# SDC_2.net
KiCad netlist of a schematic drawn in Altium Designer
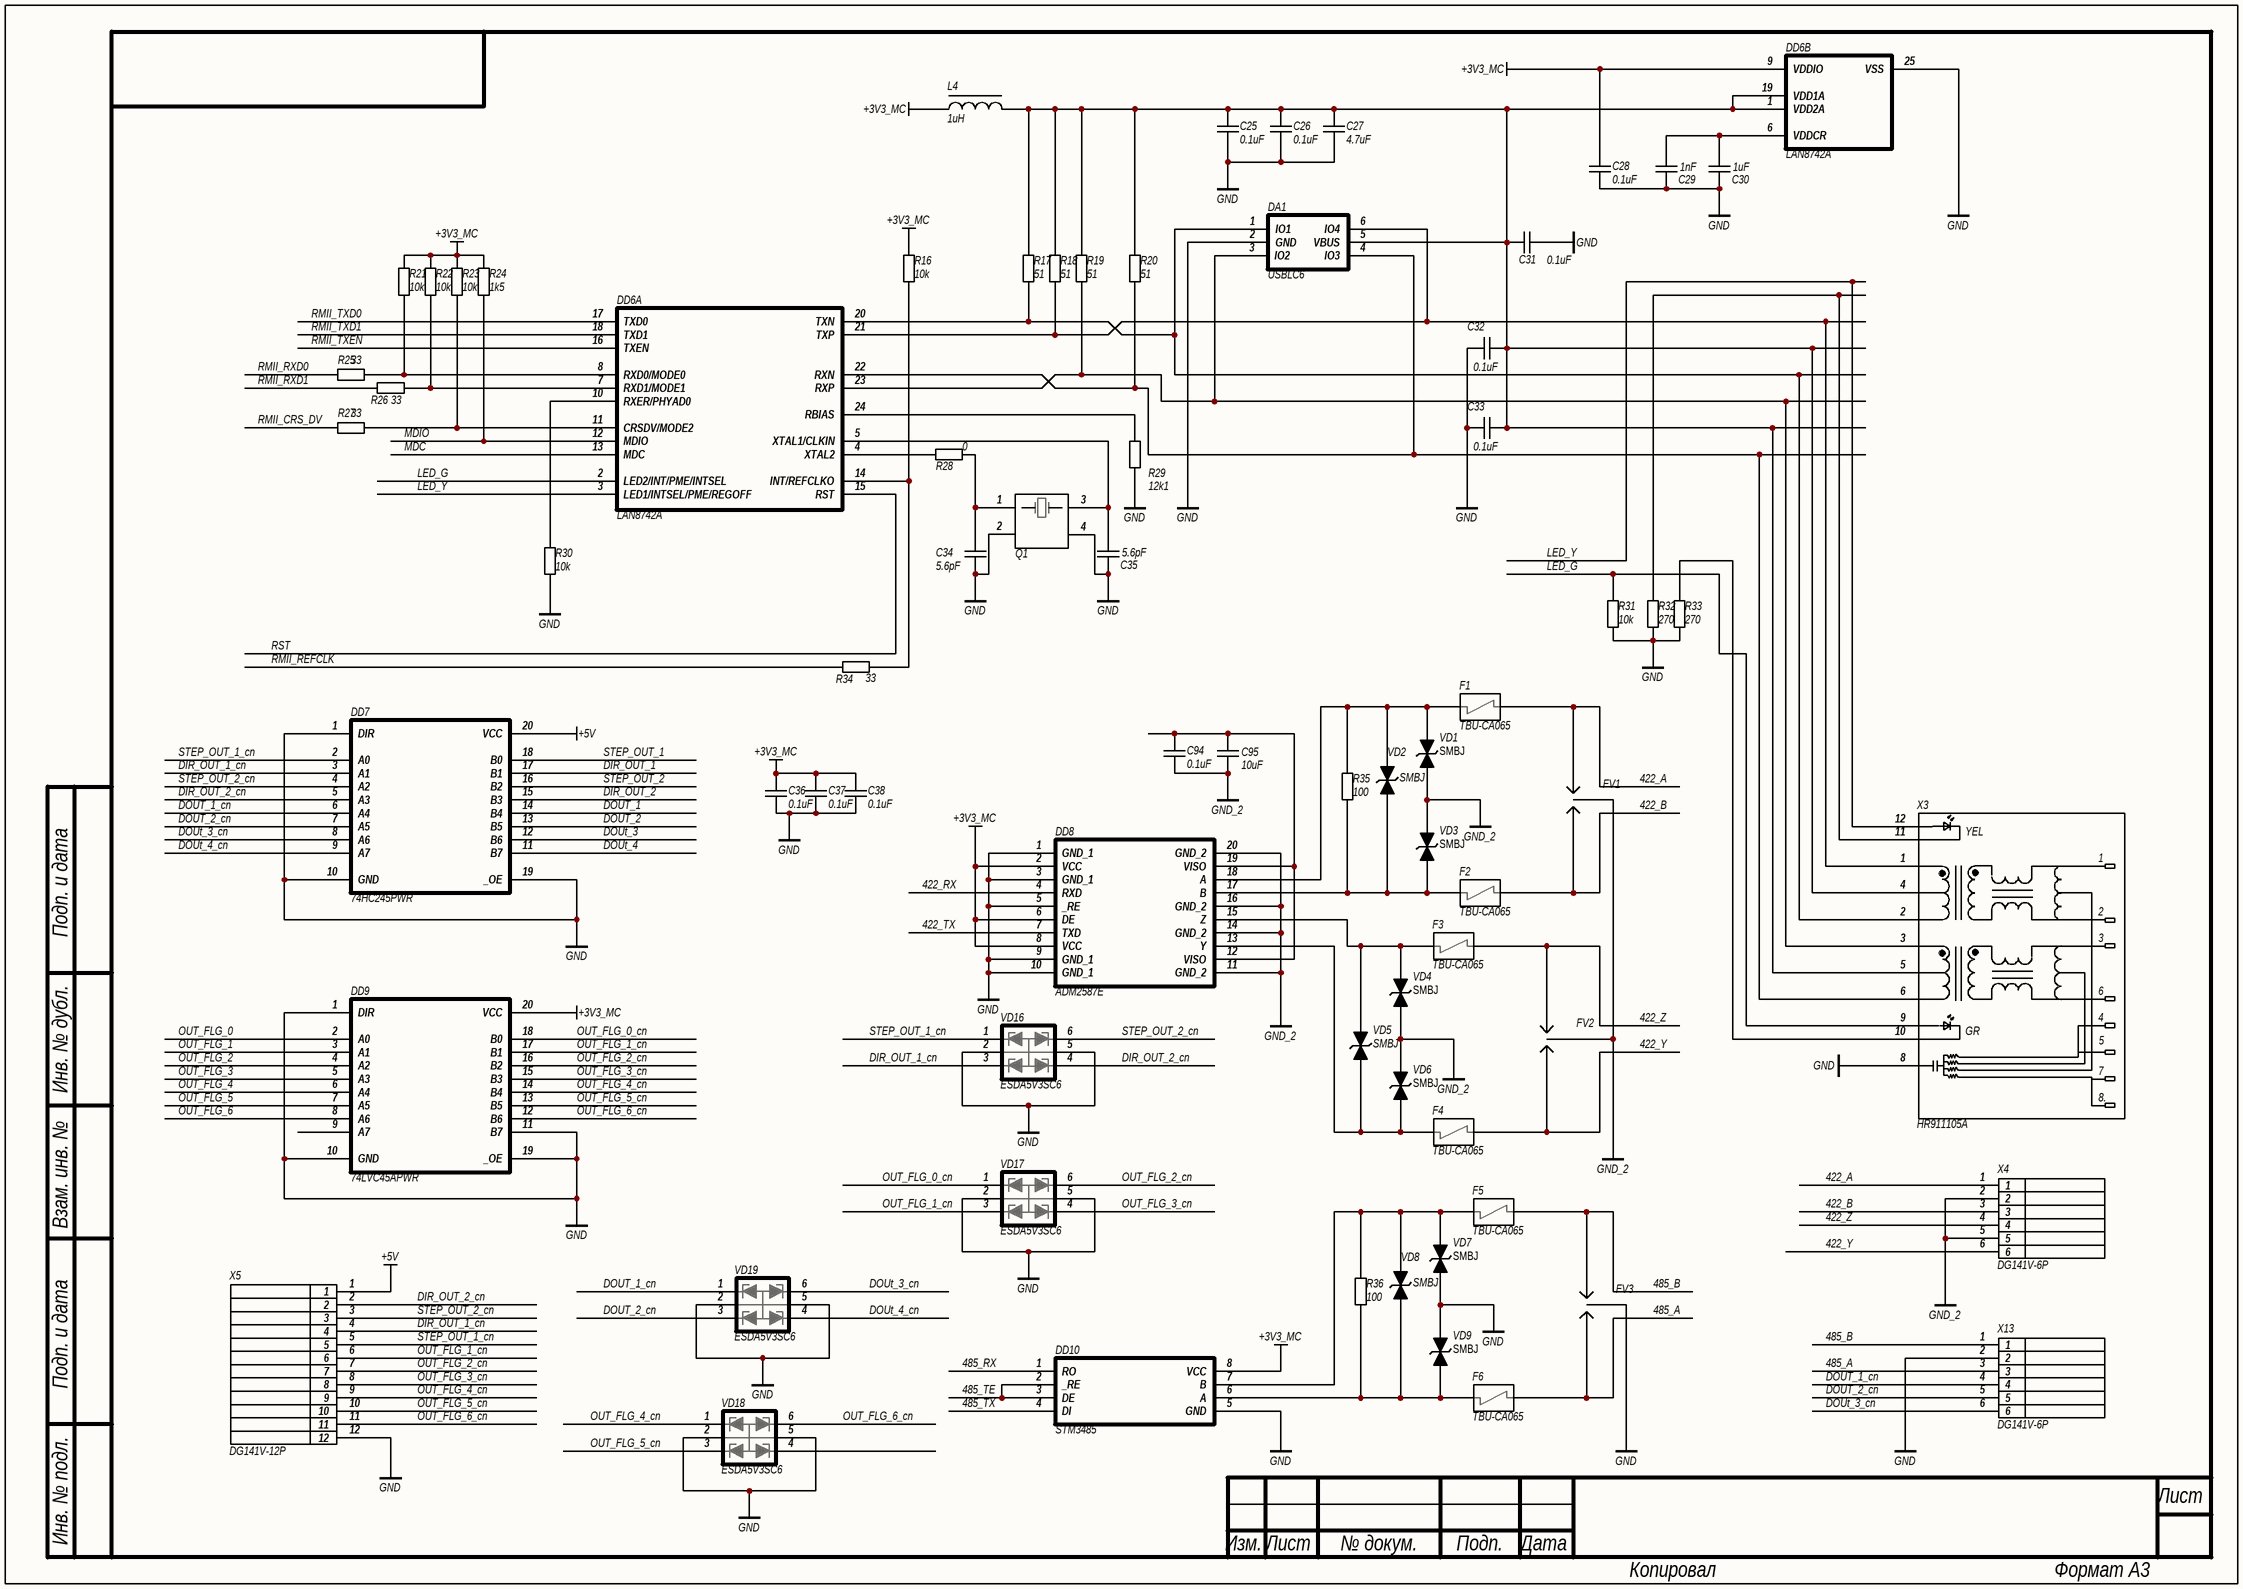
[diagram p0: SDC_2.SchDoc]

(export (version "E")
  (design (tool "Eeschema 10.0.6"))
  (components
    (comp (ref "C25")
      (value "0.1uF")
      (footprint "C0603")
      (description "SMD Capacitor")
      (fields (field (name "MANUFACTURER") "Murata") (field (name "TOLERANCE") "10%"))
      (libsource (lib "VKA") (part "CAP"))
    )
    (comp (ref "C26")
      (value "0.1uF")
      (footprint "C0603")
      (description "SMD Capacitor")
      (fields (field (name "MANUFACTURER") "Murata") (field (name "TOLERANCE") "10%"))
      (libsource (lib "VKA") (part "CAP"))
    )
    (comp (ref "C27")
      (value "4.7uF")
      (footprint "C0603")
      (description "SMD Capacitor")
      (fields (field (name "MANUFACTURER") "Murata") (field (name "TOLERANCE") "10%"))
      (libsource (lib "VKA") (part "CAP"))
    )
    (comp (ref "C28")
      (value "0.1uF")
      (footprint "C0603")
      (description "SMD Capacitor")
      (fields (field (name "MANUFACTURER") "Murata") (field (name "TOLERANCE") "10%"))
      (libsource (lib "VKA") (part "CAP"))
    )
    (comp (ref "C29")
      (value "1nF")
      (footprint "C0603")
      (description "SMD Capacitor")
      (fields (field (name "MANUFACTURER") "Murata") (field (name "TOLERANCE") "10%"))
      (libsource (lib "VKA") (part "CAP"))
    )
    (comp (ref "C30")
      (value "1uF")
      (footprint "C0603")
      (description "SMD Capacitor")
      (fields (field (name "MANUFACTURER") "Murata") (field (name "TOLERANCE") "10%"))
      (libsource (lib "VKA") (part "CAP"))
    )
    (comp (ref "C31")
      (value "0.1uF")
      (footprint "C0603")
      (description "SMD Capacitor")
      (fields (field (name "MANUFACTURER") "Murata") (field (name "TOLERANCE") "10%"))
      (libsource (lib "VKA") (part "CAP"))
    )
    (comp (ref "C32")
      (value "0.1uF")
      (footprint "C0603")
      (description "SMD Capacitor")
      (fields (field (name "MANUFACTURER") "Murata") (field (name "TOLERANCE") "10%"))
      (libsource (lib "VKA") (part "CAP"))
    )
    (comp (ref "C33")
      (value "0.1uF")
      (footprint "C0603")
      (description "SMD Capacitor")
      (fields (field (name "MANUFACTURER") "Murata") (field (name "TOLERANCE") "10%"))
      (libsource (lib "VKA") (part "CAP"))
    )
    (comp (ref "C34")
      (value "5.6pF")
      (footprint "C0603")
      (description "SMD Capacitor")
      (fields (field (name "MANUFACTURER") "Murata") (field (name "TOLERANCE") "10%"))
      (libsource (lib "VKA") (part "CAP"))
    )
    (comp (ref "C35")
      (value "5.6pF")
      (footprint "C0603")
      (description "SMD Capacitor")
      (fields (field (name "MANUFACTURER") "Murata") (field (name "TOLERANCE") "10%"))
      (libsource (lib "VKA") (part "CAP"))
    )
    (comp (ref "C36")
      (value "0.1uF")
      (footprint "C0603")
      (description "SMD Capacitor")
      (fields (field (name "MANUFACTURER") "Murata") (field (name "TOLERANCE") "10%"))
      (libsource (lib "VKA") (part "CAP"))
    )
    (comp (ref "C37")
      (value "0.1uF")
      (footprint "C0603")
      (description "SMD Capacitor")
      (fields (field (name "MANUFACTURER") "Murata") (field (name "TOLERANCE") "10%"))
      (libsource (lib "VKA") (part "CAP"))
    )
    (comp (ref "C38")
      (value "0.1uF")
      (footprint "C0603")
      (description "SMD Capacitor")
      (fields (field (name "MANUFACTURER") "Murata") (field (name "TOLERANCE") "10%"))
      (libsource (lib "VKA") (part "CAP"))
    )
    (comp (ref "C94")
      (value "0.1uF")
      (footprint "C0603")
      (description "SMD Capacitor")
      (fields (field (name "MANUFACTURER") "Murata") (field (name "TOLERANCE") "10%"))
      (libsource (lib "VKA") (part "CAP"))
    )
    (comp (ref "C95")
      (value "10uF")
      (footprint "C1210")
      (description "SMD Capacitor")
      (fields (field (name "MANUFACTURER") "Murata") (field (name "TOLERANCE") "10%"))
      (libsource (lib "VKA") (part "CAP"))
    )
    (comp (ref "DA1")
      (value "USBLC6")
      (footprint "ESD_SOT23-6L")
      (description "ESD protection Very low capacitance")
      (fields (field (name "MANUFACTURER") "ST"))
      (libsource (lib "VKA") (part "USBLC6-4SC6"))
    )
    (comp (ref "DD6")
      (value "LAN8742A")
      (footprint "QFN-MJ24")
      (description "RMII 10/100 Ethernet PHY")
      (libsource (lib "VKA") (part "LAN8742A"))
    )
    (comp (ref "DD7") (value "74HC245PWR") (footprint "TSSOP20") (libsource (lib "VKA") (part "74HC245PWR")))
    (comp (ref "DD8")
      (value "ADM2587E")
      (footprint "SOIC_20W")
      (description "RS485 isolator")
      (libsource (lib "VKA") (part "ADM2587E"))
    )
    (comp (ref "DD9")
      (value "74LVC45APWR")
      (footprint "TSSOP20")
      (libsource (lib "VKA") (part "74LVC45APWR"))
    )
    (comp (ref "DD10")
      (value "STM3485")
      (footprint "SO8_L")
      (description "RS485_tranciever")
      (libsource (lib "VKA") (part "ST3485EB"))
    )
    (comp (ref "F1")
      (value "TBU-CA065")
      (footprint "TBU-CA")
      (description "TBU fuse")
      (libsource (lib "VKA") (part "TBU-CA065"))
    )
    (comp (ref "F2")
      (value "TBU-CA065")
      (footprint "TBU-CA")
      (description "TBU fuse")
      (libsource (lib "VKA") (part "TBU-CA065"))
    )
    (comp (ref "F3")
      (value "TBU-CA065")
      (footprint "TBU-CA")
      (description "TBU fuse")
      (libsource (lib "VKA") (part "TBU-CA065"))
    )
    (comp (ref "F4")
      (value "TBU-CA065")
      (footprint "TBU-CA")
      (description "TBU fuse")
      (libsource (lib "VKA") (part "TBU-CA065"))
    )
    (comp (ref "F5")
      (value "TBU-CA065")
      (footprint "TBU-CA")
      (description "TBU fuse")
      (libsource (lib "VKA") (part "TBU-CA065"))
    )
    (comp (ref "F6")
      (value "TBU-CA065")
      (footprint "TBU-CA")
      (description "TBU fuse")
      (libsource (lib "VKA") (part "TBU-CA065"))
    )
    (comp (ref "FV1")
      (value "2030-42T-SM")
      (footprint "2030-42T-SM")
      (description "Charger")
      (libsource (lib "VKA") (part "2030-42T-SM"))
    )
    (comp (ref "FV2")
      (value "2030-42T-SM")
      (footprint "2030-42T-SM")
      (description "Charger")
      (libsource (lib "VKA") (part "2030-42T-SM"))
    )
    (comp (ref "FV3")
      (value "2030-42T-SM")
      (footprint "2030-42T-SM")
      (description "Charger")
      (libsource (lib "VKA") (part "2030-42T-SM"))
    )
    (comp (ref "L4")
      (value "1uH")
      (footprint "LQH32CN")
      (description "chip inductor")
      (fields (field (name "Comment") "LQH32CN"))
      (libsource (lib "VKA") (part "LQH32CN"))
    )
    (comp (ref "Q1")
      (value "NX2016SA")
      (footprint "CRY_NX2016SA_4P")
      (description "Crystal oscillator 25MHz")
      (fields (field (name "MANUFACTURER") "NDK"))
      (libsource (lib "VKA") (part "NX2016SA"))
    )
    (comp (ref "R16")
      (value "10k")
      (footprint "R0603")
      (description "SMD Resistor")
      (fields (field (name "POWER") "0.062 Wt") (field (name "TOLERANCE") "5%"))
      (libsource (lib "VKA") (part "RES"))
    )
    (comp (ref "R17")
      (value "51")
      (footprint "R0603")
      (description "SMD Resistor")
      (fields (field (name "POWER") "0.062 Wt") (field (name "TOLERANCE") "5%"))
      (libsource (lib "") (part "RES_1"))
    )
    (comp (ref "R18")
      (value "51")
      (footprint "R0603")
      (description "SMD Resistor")
      (fields (field (name "POWER") "0.062 Wt") (field (name "TOLERANCE") "5%"))
      (libsource (lib "") (part "RES_1"))
    )
    (comp (ref "R19")
      (value "51")
      (footprint "R0603")
      (description "SMD Resistor")
      (fields (field (name "POWER") "0.062 Wt") (field (name "TOLERANCE") "5%"))
      (libsource (lib "") (part "RES_1"))
    )
    (comp (ref "R20")
      (value "51")
      (footprint "R0603")
      (description "SMD Resistor")
      (fields (field (name "POWER") "0.062 Wt") (field (name "TOLERANCE") "5%"))
      (libsource (lib "") (part "RES_1"))
    )
    (comp (ref "R21")
      (value "10k")
      (footprint "R0603")
      (description "SMD Resistor")
      (fields (field (name "POWER") "0.062 Wt") (field (name "TOLERANCE") "5%"))
      (libsource (lib "VKA") (part "RES"))
    )
    (comp (ref "R22")
      (value "10k")
      (footprint "R0603")
      (description "SMD Resistor")
      (fields (field (name "POWER") "0.062 Wt") (field (name "TOLERANCE") "5%"))
      (libsource (lib "VKA") (part "RES"))
    )
    (comp (ref "R23")
      (value "10k")
      (footprint "R0603")
      (description "SMD Resistor")
      (fields (field (name "POWER") "0.062 Wt") (field (name "TOLERANCE") "5%"))
      (libsource (lib "VKA") (part "RES"))
    )
    (comp (ref "R24")
      (value "1k5")
      (footprint "R0603")
      (description "SMD Resistor")
      (fields (field (name "POWER") "0.062 Wt") (field (name "TOLERANCE") "5%"))
      (libsource (lib "VKA") (part "RES"))
    )
    (comp (ref "R25")
      (value "33")
      (footprint "R0603")
      (description "SMD Resistor")
      (fields (field (name "POWER") "0.062 Wt") (field (name "TOLERANCE") "5%"))
      (libsource (lib "") (part "RES_2"))
    )
    (comp (ref "R26")
      (value "33")
      (footprint "R0603")
      (description "SMD Resistor")
      (fields (field (name "POWER") "0.062 Wt") (field (name "TOLERANCE") "5%"))
      (libsource (lib "") (part "RES_2"))
    )
    (comp (ref "R27")
      (value "33")
      (footprint "R0603")
      (description "SMD Resistor")
      (fields (field (name "POWER") "0.062 Wt") (field (name "TOLERANCE") "5%"))
      (libsource (lib "") (part "RES_2"))
    )
    (comp (ref "R28")
      (value "0")
      (footprint "R0603")
      (description "SMD Resistor")
      (fields (field (name "POWER") "0.062 Wt") (field (name "TOLERANCE") "5%"))
      (libsource (lib "") (part "RES_2"))
    )
    (comp (ref "R29")
      (value "12k1")
      (footprint "R0603")
      (description "SMD Resistor")
      (fields (field (name "POWER") "0.062 Wt") (field (name "TOLERANCE") "5%"))
      (libsource (lib "") (part "RES_1"))
    )
    (comp (ref "R30")
      (value "10k")
      (footprint "R0603")
      (description "SMD Resistor")
      (fields (field (name "POWER") "0.062 Wt") (field (name "TOLERANCE") "5%"))
      (libsource (lib "") (part "RES_1"))
    )
    (comp (ref "R31")
      (value "10k")
      (footprint "R0603")
      (description "SMD Resistor")
      (fields (field (name "POWER") "0.062 Wt") (field (name "TOLERANCE") "5%"))
      (libsource (lib "") (part "RES_1"))
    )
    (comp (ref "R32")
      (value "270")
      (footprint "R0603")
      (description "SMD Resistor")
      (fields (field (name "POWER") "0.062 Wt") (field (name "TOLERANCE") "5%"))
      (libsource (lib "") (part "RES_1"))
    )
    (comp (ref "R33")
      (value "270")
      (footprint "R0603")
      (description "SMD Resistor")
      (fields (field (name "POWER") "0.062 Wt") (field (name "TOLERANCE") "5%"))
      (libsource (lib "") (part "RES_1"))
    )
    (comp (ref "R34")
      (value "33")
      (footprint "R0603")
      (description "SMD Resistor")
      (fields (field (name "POWER") "0.062 Wt") (field (name "TOLERANCE") "5%"))
      (libsource (lib "") (part "RES_2"))
    )
    (comp (ref "R35")
      (value "100")
      (footprint "R0603")
      (description "SMD Resistor")
      (fields (field (name "POWER") "0.062 Wt") (field (name "TOLERANCE") "5%"))
      (libsource (lib "VKA") (part "RES"))
    )
    (comp (ref "R36")
      (value "100")
      (footprint "R0603")
      (description "SMD Resistor")
      (fields (field (name "POWER") "0.062 Wt") (field (name "TOLERANCE") "5%"))
      (libsource (lib "VKA") (part "RES"))
    )
    (comp (ref "VD1")
      (value "SMBJ")
      (footprint "SMB-DO214")
      (description "TVS diode")
      (libsource (lib "VKA") (part "SMBJ5CA"))
    )
    (comp (ref "VD2")
      (value "SMBJ")
      (footprint "SMB-DO214")
      (description "TVSdiode")
      (libsource (lib "VKA") (part "SMBJ12CA"))
    )
    (comp (ref "VD3")
      (value "SMBJ")
      (footprint "SMB-DO214")
      (description "TVS diode")
      (libsource (lib "VKA") (part "SMBJ5CA"))
    )
    (comp (ref "VD4")
      (value "SMBJ")
      (footprint "SMB-DO214")
      (description "TVS diode")
      (libsource (lib "VKA") (part "SMBJ5CA"))
    )
    (comp (ref "VD5")
      (value "SMBJ")
      (footprint "SMB-DO214")
      (description "TVSdiode")
      (libsource (lib "VKA") (part "SMBJ12CA"))
    )
    (comp (ref "VD6")
      (value "SMBJ")
      (footprint "SMB-DO214")
      (description "TVS diode")
      (libsource (lib "VKA") (part "SMBJ5CA"))
    )
    (comp (ref "VD7")
      (value "SMBJ")
      (footprint "SMB-DO214")
      (description "TVS diode")
      (libsource (lib "VKA") (part "SMBJ5CA"))
    )
    (comp (ref "VD8")
      (value "SMBJ")
      (footprint "SMB-DO214")
      (description "TVSdiode")
      (libsource (lib "VKA") (part "SMBJ12CA"))
    )
    (comp (ref "VD9")
      (value "SMBJ")
      (footprint "SMB-DO214")
      (description "TVS diode")
      (libsource (lib "VKA") (part "SMBJ5CA"))
    )
    (comp (ref "VD16")
      (value "ESDA5V3SC6")
      (footprint "SOT23-6")
      (description "4-line ESD protection")
      (libsource (lib "VKA") (part "ESDA5V3SC6"))
    )
    (comp (ref "VD17")
      (value "ESDA5V3SC6")
      (footprint "SOT23-6")
      (description "4-line ESD protection")
      (libsource (lib "VKA") (part "ESDA5V3SC6"))
    )
    (comp (ref "VD18")
      (value "ESDA5V3SC6")
      (footprint "SOT23-6")
      (description "4-line ESD protection")
      (libsource (lib "VKA") (part "ESDA5V3SC6"))
    )
    (comp (ref "VD19")
      (value "ESDA5V3SC6")
      (footprint "SOT23-6")
      (description "4-line ESD protection")
      (libsource (lib "VKA") (part "ESDA5V3SC6"))
    )
    (comp (ref "X3") (value "HR911105A") (footprint "HR911105A") (libsource (lib "VKA") (part "HR911105A")))
    (comp (ref "X4")
      (value "DG141V-6P")
      (footprint "DG141V-06P")
      (description "wire connector")
      (libsource (lib "VKA") (part "DG141V-6P"))
    )
    (comp (ref "X5")
      (value "DG141V-12P")
      (footprint "DG141V-12P")
      (description "wire connector")
      (libsource (lib "VKA") (part "DG141V-12P"))
    )
    (comp (ref "X13")
      (value "DG141V-6P")
      (footprint "DG141V-06P")
      (description "wire connector")
      (libsource (lib "VKA") (part "DG141V-6P"))
    )
  )
  (nets
    (net (code "1") (name "+3V3_MC") (class "Default")
      (node (ref "C28") (pin "2") (pinfunction "2_2") (pintype "passive"))
      (node (ref "C36") (pin "2") (pinfunction "2_2") (pintype "passive"))
      (node (ref "C37") (pin "2") (pinfunction "2_2") (pintype "passive"))
      (node (ref "C38") (pin "2") (pinfunction "2_2") (pintype "passive"))
      (node (ref "DD10") (pin "8") (pinfunction "VCC_8") (pintype "passive"))
      (node (ref "DD6") (pin "9") (pinfunction "VDDIO_9") (pintype "passive"))
      (node (ref "DD8") (pin "2") (pinfunction "VCC_2") (pintype "passive"))
      (node (ref "DD8") (pin "6") (pinfunction "DE_6") (pintype "passive"))
      (node (ref "DD8") (pin "8") (pinfunction "VCC_8") (pintype "passive"))
      (node (ref "DD9") (pin "20") (pinfunction "VCC_20") (pintype "passive"))
      (node (ref "L4") (pin "1") (pinfunction "1_1") (pintype "passive"))
      (node (ref "R16") (pin "1") (pinfunction "1_1") (pintype "passive"))
      (node (ref "R21") (pin "1") (pinfunction "1_1") (pintype "passive"))
      (node (ref "R22") (pin "1") (pinfunction "1_1") (pintype "passive"))
      (node (ref "R23") (pin "1") (pinfunction "1_1") (pintype "passive"))
      (node (ref "R24") (pin "1") (pinfunction "1_1") (pintype "passive"))
    )
    (net (code "2") (name "+5V") (class "Default")
      (node (ref "DD7") (pin "20") (pinfunction "VCC_20") (pintype "passive"))
      (node (ref "X5") (pin "1") (pinfunction "1_1") (pintype "passive"))
    )
    (net (code "3") (name "/422_A") (class "Default")
      (node (ref "F1") (pin "2") (pinfunction "1_2") (pintype "passive"))
      (node (ref "FV1") (pin "3") (pinfunction "3_3") (pintype "passive"))
      (node (ref "X4") (pin "1") (pinfunction "1_1") (pintype "passive"))
    )
    (net (code "4") (name "/422_B") (class "Default")
      (node (ref "F2") (pin "2") (pinfunction "1_2") (pintype "passive"))
      (node (ref "FV1") (pin "1") (pinfunction "1_1") (pintype "passive"))
      (node (ref "X4") (pin "3") (pinfunction "3_3") (pintype "passive"))
    )
    (net (code "5") (name "/422_RX") (class "Default")
      (node (ref "DD8") (pin "4") (pinfunction "RXD_4") (pintype "passive"))
    )
    (net (code "6") (name "/422_TX") (class "Default")
      (node (ref "DD8") (pin "7") (pinfunction "TXD_7") (pintype "passive"))
    )
    (net (code "7") (name "/422_Y") (class "Default")
      (node (ref "F4") (pin "2") (pinfunction "1_2") (pintype "passive"))
      (node (ref "FV2") (pin "1") (pinfunction "1_1") (pintype "passive"))
      (node (ref "X4") (pin "6") (pinfunction "6_6") (pintype "passive"))
    )
    (net (code "8") (name "/422_Z") (class "Default")
      (node (ref "F3") (pin "2") (pinfunction "1_2") (pintype "passive"))
      (node (ref "FV2") (pin "3") (pinfunction "3_3") (pintype "passive"))
      (node (ref "X4") (pin "4") (pinfunction "4_4") (pintype "passive"))
    )
    (net (code "9") (name "/485_A") (class "Default")
      (node (ref "F6") (pin "2") (pinfunction "1_2") (pintype "passive"))
      (node (ref "FV3") (pin "1") (pinfunction "1_1") (pintype "passive"))
      (node (ref "X13") (pin "3") (pinfunction "3_3") (pintype "passive"))
    )
    (net (code "10") (name "/485_B") (class "Default")
      (node (ref "F5") (pin "2") (pinfunction "1_2") (pintype "passive"))
      (node (ref "FV3") (pin "3") (pinfunction "3_3") (pintype "passive"))
      (node (ref "X13") (pin "1") (pinfunction "1_1") (pintype "passive"))
    )
    (net (code "11") (name "/485_RX") (class "Default")
      (node (ref "DD10") (pin "1") (pinfunction "RO_1") (pintype "passive"))
    )
    (net (code "12") (name "/485_TE") (class "Default")
      (node (ref "DD10") (pin "2") (pinfunction "_RE_2") (pintype "passive"))
      (node (ref "DD10") (pin "3") (pinfunction "DE_3") (pintype "passive"))
    )
    (net (code "13") (name "/485_TX") (class "Default")
      (node (ref "DD10") (pin "4") (pinfunction "DI_4") (pintype "passive"))
    )
    (net (code "14") (name "/DIR_OUT_1") (class "Default")
      (node (ref "DD7") (pin "17") (pinfunction "B1_17") (pintype "passive"))
    )
    (net (code "15") (name "/DIR_OUT_1_cn") (class "Default")
      (node (ref "DD7") (pin "3") (pinfunction "A1_3") (pintype "passive"))
      (node (ref "VD16") (pin "3") (pinfunction "3_3") (pintype "passive"))
      (node (ref "X5") (pin "4") (pinfunction "4_4") (pintype "passive"))
    )
    (net (code "16") (name "/DIR_OUT_2") (class "Default")
      (node (ref "DD7") (pin "15") (pinfunction "B3_15") (pintype "passive"))
    )
    (net (code "17") (name "/DIR_OUT_2_cn") (class "Default")
      (node (ref "DD7") (pin "5") (pinfunction "A3_5") (pintype "passive"))
      (node (ref "VD16") (pin "4") (pinfunction "4_4") (pintype "passive"))
      (node (ref "X5") (pin "2") (pinfunction "2_2") (pintype "passive"))
    )
    (net (code "18") (name "/DOUT_1") (class "Default")
      (node (ref "DD7") (pin "14") (pinfunction "B4_14") (pintype "passive"))
    )
    (net (code "19") (name "/DOUT_1_cn") (class "Default")
      (node (ref "DD7") (pin "6") (pinfunction "A4_6") (pintype "passive"))
      (node (ref "VD19") (pin "1") (pinfunction "1_1") (pintype "passive"))
      (node (ref "X13") (pin "4") (pinfunction "4_4") (pintype "passive"))
    )
    (net (code "20") (name "/DOUT_2") (class "Default")
      (node (ref "DD7") (pin "13") (pinfunction "B5_13") (pintype "passive"))
    )
    (net (code "21") (name "/DOUT_2_cn") (class "Default")
      (node (ref "DD7") (pin "7") (pinfunction "A5_7") (pintype "passive"))
      (node (ref "VD19") (pin "3") (pinfunction "3_3") (pintype "passive"))
      (node (ref "X13") (pin "5") (pinfunction "5_5") (pintype "passive"))
    )
    (net (code "22") (name "/DOUt_3") (class "Default")
      (node (ref "DD7") (pin "12") (pinfunction "B6_12") (pintype "passive"))
    )
    (net (code "23") (name "/DOUt_3_cn") (class "Default")
      (node (ref "DD7") (pin "8") (pinfunction "A6_8") (pintype "passive"))
      (node (ref "VD19") (pin "6") (pinfunction "6_6") (pintype "passive"))
      (node (ref "X13") (pin "6") (pinfunction "6_6") (pintype "passive"))
    )
    (net (code "24") (name "/DOUt_4") (class "Default")
      (node (ref "DD7") (pin "11") (pinfunction "B7_11") (pintype "passive"))
    )
    (net (code "25") (name "/DOUt_4_cn") (class "Default")
      (node (ref "DD7") (pin "9") (pinfunction "A7_9") (pintype "passive"))
      (node (ref "VD19") (pin "4") (pinfunction "4_4") (pintype "passive"))
    )
    (net (code "26") (name "/LED_G") (class "Default")
      (node (ref "DD6") (pin "2") (pinfunction "LED2/INT/PME/INTSEL_2") (pintype "passive"))
      (node (ref "R31") (pin "2") (pinfunction "2_2") (pintype "passive"))
      (node (ref "X3") (pin "9") (pinfunction "9_9") (pintype "passive"))
    )
    (net (code "27") (name "/LED_Y") (class "Default")
      (node (ref "DD6") (pin "3") (pinfunction "LED1/INTSEL/PME/REGOFF_3") (pintype "passive"))
      (node (ref "X3") (pin "12") (pinfunction "12_12") (pintype "passive"))
    )
    (net (code "28") (name "/MDC") (class "Default")
      (node (ref "DD6") (pin "13") (pinfunction "MDC_13") (pintype "passive"))
    )
    (net (code "29") (name "/MDIO") (class "Default")
      (node (ref "DD6") (pin "12") (pinfunction "MDIO_12") (pintype "passive"))
      (node (ref "R24") (pin "2") (pinfunction "2_2") (pintype "passive"))
    )
    (net (code "30") (name "/OUT_FLG_0") (class "Default")
      (node (ref "DD9") (pin "2") (pinfunction "A0_2") (pintype "passive"))
    )
    (net (code "31") (name "/OUT_FLG_0_cn") (class "Default")
      (node (ref "DD9") (pin "18") (pinfunction "B0_18") (pintype "passive"))
      (node (ref "VD17") (pin "1") (pinfunction "1_1") (pintype "passive"))
    )
    (net (code "32") (name "/OUT_FLG_1") (class "Default")
      (node (ref "DD9") (pin "3") (pinfunction "A1_3") (pintype "passive"))
    )
    (net (code "33") (name "/OUT_FLG_1_cn") (class "Default")
      (node (ref "DD9") (pin "17") (pinfunction "B1_17") (pintype "passive"))
      (node (ref "VD17") (pin "3") (pinfunction "3_3") (pintype "passive"))
      (node (ref "X5") (pin "6") (pinfunction "6_6") (pintype "passive"))
    )
    (net (code "34") (name "/OUT_FLG_2") (class "Default")
      (node (ref "DD9") (pin "4") (pinfunction "A2_4") (pintype "passive"))
    )
    (net (code "35") (name "/OUT_FLG_2_cn") (class "Default")
      (node (ref "DD9") (pin "16") (pinfunction "B2_16") (pintype "passive"))
      (node (ref "VD17") (pin "6") (pinfunction "6_6") (pintype "passive"))
      (node (ref "X5") (pin "7") (pinfunction "7_7") (pintype "passive"))
    )
    (net (code "36") (name "/OUT_FLG_3") (class "Default")
      (node (ref "DD9") (pin "5") (pinfunction "A3_5") (pintype "passive"))
    )
    (net (code "37") (name "/OUT_FLG_3_cn") (class "Default")
      (node (ref "DD9") (pin "15") (pinfunction "B3_15") (pintype "passive"))
      (node (ref "VD17") (pin "4") (pinfunction "4_4") (pintype "passive"))
      (node (ref "X5") (pin "8") (pinfunction "8_8") (pintype "passive"))
    )
    (net (code "38") (name "/OUT_FLG_4") (class "Default")
      (node (ref "DD9") (pin "6") (pinfunction "A4_6") (pintype "passive"))
    )
    (net (code "39") (name "/OUT_FLG_4_cn") (class "Default")
      (node (ref "DD9") (pin "14") (pinfunction "B4_14") (pintype "passive"))
      (node (ref "VD18") (pin "1") (pinfunction "1_1") (pintype "passive"))
      (node (ref "X5") (pin "9") (pinfunction "9_9") (pintype "passive"))
    )
    (net (code "40") (name "/OUT_FLG_5") (class "Default")
      (node (ref "DD9") (pin "7") (pinfunction "A5_7") (pintype "passive"))
    )
    (net (code "41") (name "/OUT_FLG_5_cn") (class "Default")
      (node (ref "DD9") (pin "13") (pinfunction "B5_13") (pintype "passive"))
      (node (ref "VD18") (pin "3") (pinfunction "3_3") (pintype "passive"))
      (node (ref "X5") (pin "10") (pinfunction "10_10") (pintype "passive"))
    )
    (net (code "42") (name "/OUT_FLG_6") (class "Default")
      (node (ref "DD9") (pin "8") (pinfunction "A6_8") (pintype "passive"))
    )
    (net (code "43") (name "/OUT_FLG_6_cn") (class "Default")
      (node (ref "DD9") (pin "12") (pinfunction "B6_12") (pintype "passive"))
      (node (ref "VD18") (pin "6") (pinfunction "6_6") (pintype "passive"))
      (node (ref "X5") (pin "11") (pinfunction "11_11") (pintype "passive"))
    )
    (net (code "44") (name "/RMII_CRS_DV") (class "Default")
      (node (ref "R27") (pin "2") (pinfunction "2_2") (pintype "passive"))
    )
    (net (code "45") (name "/RMII_REFCLK") (class "Default")
      (node (ref "R34") (pin "2") (pinfunction "2_2") (pintype "passive"))
    )
    (net (code "46") (name "/RMII_RXD0") (class "Default")
      (node (ref "R25") (pin "2") (pinfunction "2_2") (pintype "passive"))
    )
    (net (code "47") (name "/RMII_RXD1") (class "Default")
      (node (ref "R26") (pin "2") (pinfunction "2_2") (pintype "passive"))
    )
    (net (code "48") (name "/RMII_TXD0") (class "Default")
      (node (ref "DD6") (pin "17") (pinfunction "TXD0_17") (pintype "passive"))
    )
    (net (code "49") (name "/RMII_TXD1") (class "Default")
      (node (ref "DD6") (pin "18") (pinfunction "TXD1_18") (pintype "passive"))
    )
    (net (code "50") (name "/RMII_TXEN") (class "Default")
      (node (ref "DD6") (pin "16") (pinfunction "TXEN_16") (pintype "passive"))
    )
    (net (code "51") (name "/RST") (class "Default")
      (node (ref "DD6") (pin "15") (pinfunction "RST_15") (pintype "passive"))
    )
    (net (code "52") (name "/STEP_OUT_1") (class "Default")
      (node (ref "DD7") (pin "18") (pinfunction "B0_18") (pintype "passive"))
    )
    (net (code "53") (name "/STEP_OUT_1_cn") (class "Default")
      (node (ref "DD7") (pin "2") (pinfunction "A0_2") (pintype "passive"))
      (node (ref "VD16") (pin "1") (pinfunction "1_1") (pintype "passive"))
      (node (ref "X5") (pin "5") (pinfunction "5_5") (pintype "passive"))
    )
    (net (code "54") (name "/STEP_OUT_2") (class "Default")
      (node (ref "DD7") (pin "16") (pinfunction "B2_16") (pintype "passive"))
    )
    (net (code "55") (name "/STEP_OUT_2_cn") (class "Default")
      (node (ref "DD7") (pin "4") (pinfunction "A2_4") (pintype "passive"))
      (node (ref "VD16") (pin "6") (pinfunction "6_6") (pintype "passive"))
      (node (ref "X5") (pin "3") (pinfunction "3_3") (pintype "passive"))
    )
    (net (code "56") (name "GND") (class "Default")
      (node (ref "C25") (pin "1") (pinfunction "1_1") (pintype "passive"))
      (node (ref "C26") (pin "1") (pinfunction "1_1") (pintype "passive"))
      (node (ref "C27") (pin "1") (pinfunction "1_1") (pintype "passive"))
      (node (ref "C28") (pin "1") (pinfunction "1_1") (pintype "passive"))
      (node (ref "C29") (pin "1") (pinfunction "1_1") (pintype "passive"))
      (node (ref "C30") (pin "1") (pinfunction "1_1") (pintype "passive"))
      (node (ref "C31") (pin "2") (pinfunction "2_2") (pintype "passive"))
      (node (ref "C32") (pin "1") (pinfunction "1_1") (pintype "passive"))
      (node (ref "C33") (pin "1") (pinfunction "1_1") (pintype "passive"))
      (node (ref "C34") (pin "1") (pinfunction "1_1") (pintype "passive"))
      (node (ref "C35") (pin "1") (pinfunction "1_1") (pintype "passive"))
      (node (ref "C36") (pin "1") (pinfunction "1_1") (pintype "passive"))
      (node (ref "C37") (pin "1") (pinfunction "1_1") (pintype "passive"))
      (node (ref "C38") (pin "1") (pinfunction "1_1") (pintype "passive"))
      (node (ref "DA1") (pin "2") (pinfunction "GND_2") (pintype "passive"))
      (node (ref "DD10") (pin "5") (pinfunction "GND_5") (pintype "passive"))
      (node (ref "DD6") (pin "25") (pinfunction "VSS_25") (pintype "passive"))
      (node (ref "DD7") (pin "1") (pinfunction "DIR_1") (pintype "passive"))
      (node (ref "DD7") (pin "10") (pinfunction "GND_10") (pintype "passive"))
      (node (ref "DD7") (pin "19") (pinfunction "_OE_19") (pintype "passive"))
      (node (ref "DD8") (pin "1") (pinfunction "GND_1_1") (pintype "passive"))
      (node (ref "DD8") (pin "10") (pinfunction "GND_1_10") (pintype "passive"))
      (node (ref "DD8") (pin "3") (pinfunction "GND_1_3") (pintype "passive"))
      (node (ref "DD8") (pin "5") (pinfunction "_RE_5") (pintype "passive"))
      (node (ref "DD8") (pin "9") (pinfunction "GND_1_9") (pintype "passive"))
      (node (ref "DD9") (pin "1") (pinfunction "DIR_1") (pintype "passive"))
      (node (ref "DD9") (pin "10") (pinfunction "GND_10") (pintype "passive"))
      (node (ref "DD9") (pin "11") (pinfunction "B7_11") (pintype "passive"))
      (node (ref "DD9") (pin "19") (pinfunction "_OE_19") (pintype "passive"))
      (node (ref "FV3") (pin "2") (pinfunction "2_2") (pintype "passive"))
      (node (ref "Q1") (pin "2") (pinfunction "OSC1_2") (pintype "passive"))
      (node (ref "Q1") (pin "4") (pinfunction "OSC1_4") (pintype "passive"))
      (node (ref "R29") (pin "1") (pinfunction "1_1") (pintype "passive"))
      (node (ref "R30") (pin "1") (pinfunction "1_1") (pintype "passive"))
      (node (ref "R31") (pin "1") (pinfunction "1_1") (pintype "passive"))
      (node (ref "R32") (pin "1") (pinfunction "1_1") (pintype "passive"))
      (node (ref "R33") (pin "1") (pinfunction "1_1") (pintype "passive"))
      (node (ref "VD16") (pin "2") (pinfunction "2_2") (pintype "passive"))
      (node (ref "VD16") (pin "5") (pinfunction "5_5") (pintype "passive"))
      (node (ref "VD17") (pin "2") (pinfunction "2_2") (pintype "passive"))
      (node (ref "VD17") (pin "5") (pinfunction "5_5") (pintype "passive"))
      (node (ref "VD18") (pin "2") (pinfunction "2_2") (pintype "passive"))
      (node (ref "VD18") (pin "5") (pinfunction "5_5") (pintype "passive"))
      (node (ref "VD19") (pin "2") (pinfunction "2_2") (pintype "passive"))
      (node (ref "VD19") (pin "5") (pinfunction "5_5") (pintype "passive"))
      (node (ref "VD7") (pin "1") (pinfunction "A_1") (pintype "passive"))
      (node (ref "VD9") (pin "2") (pinfunction "B_2") (pintype "passive"))
      (node (ref "X13") (pin "2") (pinfunction "2_2") (pintype "passive"))
      (node (ref "X3") (pin "8") (pinfunction "8_8") (pintype "passive"))
      (node (ref "X5") (pin "12") (pinfunction "12_12") (pintype "passive"))
    )
    (net (code "57") (name "GND_2") (class "Default")
      (node (ref "C94") (pin "1") (pinfunction "1_1") (pintype "passive"))
      (node (ref "C95") (pin "1") (pinfunction "1_1") (pintype "passive"))
      (node (ref "DD8") (pin "11") (pinfunction "GND_2_11") (pintype "passive"))
      (node (ref "DD8") (pin "14") (pinfunction "GND_2_14") (pintype "passive"))
      (node (ref "DD8") (pin "16") (pinfunction "GND_2_16") (pintype "passive"))
      (node (ref "DD8") (pin "20") (pinfunction "GND_2_20") (pintype "passive"))
      (node (ref "FV1") (pin "2") (pinfunction "2_2") (pintype "passive"))
      (node (ref "FV2") (pin "2") (pinfunction "2_2") (pintype "passive"))
      (node (ref "VD1") (pin "1") (pinfunction "A_1") (pintype "passive"))
      (node (ref "VD3") (pin "2") (pinfunction "B_2") (pintype "passive"))
      (node (ref "VD4") (pin "1") (pinfunction "A_1") (pintype "passive"))
      (node (ref "VD6") (pin "2") (pinfunction "B_2") (pintype "passive"))
      (node (ref "X4") (pin "2") (pinfunction "2_2") (pintype "passive"))
      (node (ref "X4") (pin "5") (pinfunction "5_5") (pintype "passive"))
    )
    (net (code "58") (name "Net-(C34-Pad2)") (class "Default")
      (node (ref "C34") (pin "2") (pinfunction "2_2") (pintype "passive"))
      (node (ref "Q1") (pin "1") (pinfunction "OSC1_1") (pintype "passive"))
      (node (ref "R28") (pin "1") (pinfunction "1_1") (pintype "passive"))
    )
    (net (code "59") (name "Net-(C94-Pad2)") (class "Default")
      (node (ref "C94") (pin "2") (pinfunction "2_2") (pintype "passive"))
      (node (ref "C95") (pin "2") (pinfunction "2_2") (pintype "passive"))
      (node (ref "DD8") (pin "12") (pinfunction "VISO_12") (pintype "passive"))
      (node (ref "DD8") (pin "19") (pinfunction "VISO_19") (pintype "passive"))
    )
    (net (code "60") (name "Net-(DA1-IO1)") (class "Default")
      (node (ref "DA1") (pin "1") (pinfunction "IO1_1") (pintype "passive"))
      (node (ref "DD6") (pin "20") (pinfunction "TXN_20") (pintype "passive"))
      (node (ref "R17") (pin "1") (pinfunction "1_1") (pintype "passive"))
      (node (ref "X3") (pin "2") (pinfunction "2_2") (pintype "passive"))
    )
    (net (code "61") (name "Net-(DA1-IO2)") (class "Default")
      (node (ref "DA1") (pin "3") (pinfunction "IO2_3") (pintype "passive"))
      (node (ref "DD6") (pin "23") (pinfunction "RXP_23") (pintype "passive"))
      (node (ref "R19") (pin "1") (pinfunction "1_1") (pintype "passive"))
      (node (ref "X3") (pin "3") (pinfunction "3_3") (pintype "passive"))
    )
    (net (code "62") (name "Net-(DA1-IO3)") (class "Default")
      (node (ref "DA1") (pin "4") (pinfunction "IO3_4") (pintype "passive"))
      (node (ref "DD6") (pin "22") (pinfunction "RXN_22") (pintype "passive"))
      (node (ref "R20") (pin "1") (pinfunction "1_1") (pintype "passive"))
      (node (ref "X3") (pin "6") (pinfunction "6_6") (pintype "passive"))
    )
    (net (code "63") (name "Net-(DA1-IO4)") (class "Default")
      (node (ref "DA1") (pin "6") (pinfunction "IO4_6") (pintype "passive"))
      (node (ref "DD6") (pin "21") (pinfunction "TXP_21") (pintype "passive"))
      (node (ref "R18") (pin "1") (pinfunction "1_1") (pintype "passive"))
      (node (ref "X3") (pin "1") (pinfunction "1_1") (pintype "passive"))
    )
    (net (code "64") (name "Net-(DA1-VBUS)") (class "Default")
      (node (ref "C25") (pin "2") (pinfunction "2_2") (pintype "passive"))
      (node (ref "C26") (pin "2") (pinfunction "2_2") (pintype "passive"))
      (node (ref "C27") (pin "2") (pinfunction "2_2") (pintype "passive"))
      (node (ref "C31") (pin "1") (pinfunction "1_1") (pintype "passive"))
      (node (ref "C32") (pin "2") (pinfunction "2_2") (pintype "passive"))
      (node (ref "C33") (pin "2") (pinfunction "2_2") (pintype "passive"))
      (node (ref "DA1") (pin "5") (pinfunction "VBUS_5") (pintype "passive"))
      (node (ref "DD6") (pin "1") (pinfunction "VDD2A_1") (pintype "passive"))
      (node (ref "DD6") (pin "19") (pinfunction "VDD1A_19") (pintype "passive"))
      (node (ref "L4") (pin "2") (pinfunction "2_2") (pintype "passive"))
      (node (ref "R17") (pin "2") (pinfunction "2_2") (pintype "passive"))
      (node (ref "R18") (pin "2") (pinfunction "2_2") (pintype "passive"))
      (node (ref "R19") (pin "2") (pinfunction "2_2") (pintype "passive"))
      (node (ref "R20") (pin "2") (pinfunction "2_2") (pintype "passive"))
      (node (ref "X3") (pin "4") (pinfunction "4_4") (pintype "passive"))
      (node (ref "X3") (pin "5") (pinfunction "5_5") (pintype "passive"))
    )
    (net (code "65") (name "Net-(DD6A-CRSDV{slash}MODE2)") (class "Default")
      (node (ref "DD6") (pin "11") (pinfunction "CRSDV/MODE2_11") (pintype "passive"))
      (node (ref "R23") (pin "2") (pinfunction "2_2") (pintype "passive"))
      (node (ref "R27") (pin "1") (pinfunction "1_1") (pintype "passive"))
    )
    (net (code "66") (name "Net-(DD6A-INT{slash}REFCLKO)") (class "Default")
      (node (ref "DD6") (pin "14") (pinfunction "INT/REFCLKO_14") (pintype "passive"))
      (node (ref "R16") (pin "2") (pinfunction "2_2") (pintype "passive"))
      (node (ref "R34") (pin "1") (pinfunction "1_1") (pintype "passive"))
    )
    (net (code "67") (name "Net-(DD6A-RBIAS)") (class "Default")
      (node (ref "DD6") (pin "24") (pinfunction "RBIAS_24") (pintype "passive"))
      (node (ref "R29") (pin "2") (pinfunction "2_2") (pintype "passive"))
    )
    (net (code "68") (name "Net-(DD6A-RXD0{slash}MODE0)") (class "Default")
      (node (ref "DD6") (pin "8") (pinfunction "RXD0/MODE0_8") (pintype "passive"))
      (node (ref "R21") (pin "2") (pinfunction "2_2") (pintype "passive"))
      (node (ref "R25") (pin "1") (pinfunction "1_1") (pintype "passive"))
    )
    (net (code "69") (name "Net-(DD6A-RXD1{slash}MODE1)") (class "Default")
      (node (ref "DD6") (pin "7") (pinfunction "RXD1/MODE1_7") (pintype "passive"))
      (node (ref "R22") (pin "2") (pinfunction "2_2") (pintype "passive"))
      (node (ref "R26") (pin "1") (pinfunction "1_1") (pintype "passive"))
    )
    (net (code "70") (name "Net-(DD6A-RXER{slash}PHYAD0)") (class "Default")
      (node (ref "DD6") (pin "10") (pinfunction "RXER/PHYAD0_10") (pintype "passive"))
      (node (ref "R30") (pin "2") (pinfunction "2_2") (pintype "passive"))
    )
    (net (code "71") (name "Net-(DD6A-XTAL1{slash}CLKIN)") (class "Default")
      (node (ref "C35") (pin "2") (pinfunction "2_2") (pintype "passive"))
      (node (ref "DD6") (pin "5") (pinfunction "XTAL1/CLKIN_5") (pintype "passive"))
      (node (ref "Q1") (pin "3") (pinfunction "OSC2_3") (pintype "passive"))
    )
    (net (code "72") (name "Net-(DD6A-XTAL2)") (class "Default")
      (node (ref "DD6") (pin "4") (pinfunction "XTAL2_4") (pintype "passive"))
      (node (ref "R28") (pin "2") (pinfunction "2_2") (pintype "passive"))
    )
    (net (code "73") (name "Net-(DD6B-VDDCR)") (class "Default")
      (node (ref "C29") (pin "2") (pinfunction "2_2") (pintype "passive"))
      (node (ref "C30") (pin "2") (pinfunction "2_2") (pintype "passive"))
      (node (ref "DD6") (pin "6") (pinfunction "VDDCR_6") (pintype "passive"))
    )
    (net (code "74") (name "Net-(DD8-A)") (class "Default")
      (node (ref "DD8") (pin "18") (pinfunction "A_18") (pintype "passive"))
      (node (ref "F1") (pin "1") (pinfunction "1_1") (pintype "passive"))
      (node (ref "R35") (pin "1") (pinfunction "1_1") (pintype "passive"))
      (node (ref "VD1") (pin "2") (pinfunction "B_2") (pintype "passive"))
      (node (ref "VD2") (pin "2") (pinfunction "B_2") (pintype "passive"))
    )
    (net (code "75") (name "Net-(DD8-B)") (class "Default")
      (node (ref "DD8") (pin "17") (pinfunction "B_17") (pintype "passive"))
      (node (ref "F2") (pin "1") (pinfunction "1_1") (pintype "passive"))
      (node (ref "R35") (pin "2") (pinfunction "2_2") (pintype "passive"))
      (node (ref "VD2") (pin "1") (pinfunction "A_1") (pintype "passive"))
      (node (ref "VD3") (pin "1") (pinfunction "A_1") (pintype "passive"))
    )
    (net (code "76") (name "Net-(DD8-Y)") (class "Default")
      (node (ref "DD8") (pin "13") (pinfunction "Y_13") (pintype "passive"))
      (node (ref "F4") (pin "1") (pinfunction "1_1") (pintype "passive"))
      (node (ref "VD5") (pin "1") (pinfunction "A_1") (pintype "passive"))
      (node (ref "VD6") (pin "1") (pinfunction "A_1") (pintype "passive"))
    )
    (net (code "77") (name "Net-(DD8-Z)") (class "Default")
      (node (ref "DD8") (pin "15") (pinfunction "Z_15") (pintype "passive"))
      (node (ref "F3") (pin "1") (pinfunction "1_1") (pintype "passive"))
      (node (ref "VD4") (pin "2") (pinfunction "B_2") (pintype "passive"))
      (node (ref "VD5") (pin "2") (pinfunction "B_2") (pintype "passive"))
    )
    (net (code "78") (name "Net-(DD10-A)") (class "Default")
      (node (ref "DD10") (pin "6") (pinfunction "A_6") (pintype "passive"))
      (node (ref "F6") (pin "1") (pinfunction "1_1") (pintype "passive"))
      (node (ref "R36") (pin "2") (pinfunction "2_2") (pintype "passive"))
      (node (ref "VD8") (pin "1") (pinfunction "A_1") (pintype "passive"))
      (node (ref "VD9") (pin "1") (pinfunction "A_1") (pintype "passive"))
    )
    (net (code "79") (name "Net-(DD10-B)") (class "Default")
      (node (ref "DD10") (pin "7") (pinfunction "B_7") (pintype "passive"))
      (node (ref "F5") (pin "1") (pinfunction "1_1") (pintype "passive"))
      (node (ref "R36") (pin "1") (pinfunction "1_1") (pintype "passive"))
      (node (ref "VD7") (pin "2") (pinfunction "B_2") (pintype "passive"))
      (node (ref "VD8") (pin "2") (pinfunction "B_2") (pintype "passive"))
    )
    (net (code "80") (name "Net-(R32-Pad2)") (class "Default")
      (node (ref "R32") (pin "2") (pinfunction "2_2") (pintype "passive"))
      (node (ref "X3") (pin "11") (pinfunction "11_11") (pintype "passive"))
    )
    (net (code "81") (name "Net-(R33-Pad2)") (class "Default")
      (node (ref "R33") (pin "2") (pinfunction "2_2") (pintype "passive"))
      (node (ref "X3") (pin "10") (pinfunction "10_10") (pintype "passive"))
    )
    (net (code "82") (name "unconnected-(DD9-A7-Pad9)") (class "Default")
      (node (ref "DD9") (pin "9") (pinfunction "A7_9") (pintype "passive"))
    )
    (net (code "83") (name "unconnected-(VD18-Pad4)") (class "Default")
      (node (ref "VD18") (pin "4") (pinfunction "4_4") (pintype "passive"))
    )
  )
)
